# tivaAdapterPcb.net
KiCad netlist of a schematic drawn in EAGLE
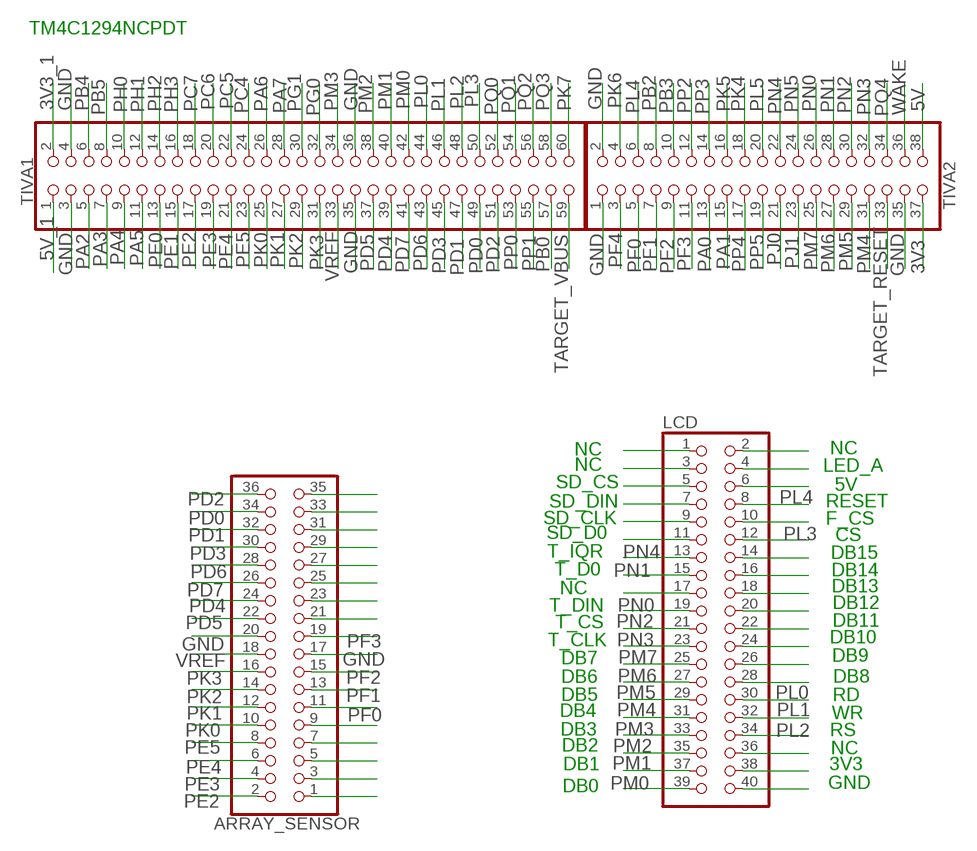
[diagram p0: schematic, sheet 1]

(export (version "E")
  (design (tool "Eeschema 10.0.6"))
  (components
    (comp (ref "ARRAY_SENSOR")
      (value "PINHD-2X18")
      (footprint "eagle-import:2X18")
      (libsource (lib "eagle-import") (part "PINHD-2X18"))
    )
    (comp (ref "LCD")
      (value "PINHD-2X20")
      (footprint "eagle-import:2X20")
      (libsource (lib "eagle-import") (part "PINHD-2X20"))
    )
    (comp (ref "TIVA1")
      (value "PINHD-2X30")
      (footprint "eagle-import:2X30")
      (libsource (lib "eagle-import") (part "PINHD-2X30"))
    )
    (comp (ref "TIVA2")
      (value "PINHD-2X19")
      (footprint "eagle-import:2X19")
      (libsource (lib "eagle-import") (part "PINHD-2X19"))
    )
  )
  (nets
    (net (code "1") (name "/3V3") (class "Default")
      (node (ref "TIVA2") (pin "37") (pinfunction "37_37") (pintype "passive"))
    )
    (net (code "2") (name "/3V3_1") (class "Default")
      (node (ref "TIVA1") (pin "2") (pinfunction "2_2") (pintype "passive"))
    )
    (net (code "3") (name "/5V") (class "Default")
      (node (ref "TIVA2") (pin "38") (pinfunction "38_38") (pintype "passive"))
    )
    (net (code "4") (name "/5V_1") (class "Default")
      (node (ref "TIVA1") (pin "1") (pinfunction "1_1") (pintype "passive"))
    )
    (net (code "5") (name "/GND") (class "Default")
      (node (ref "ARRAY_SENSOR") (pin "17") (pinfunction "17_17") (pintype "passive"))
      (node (ref "ARRAY_SENSOR") (pin "20") (pinfunction "20_20") (pintype "passive"))
      (node (ref "TIVA1") (pin "3") (pinfunction "3_3") (pintype "passive"))
      (node (ref "TIVA1") (pin "35") (pinfunction "35_35") (pintype "passive"))
      (node (ref "TIVA1") (pin "36") (pinfunction "36_36") (pintype "passive"))
      (node (ref "TIVA1") (pin "4") (pinfunction "4_4") (pintype "passive"))
      (node (ref "TIVA2") (pin "1") (pinfunction "1_1") (pintype "passive"))
      (node (ref "TIVA2") (pin "2") (pinfunction "2_2") (pintype "passive"))
      (node (ref "TIVA2") (pin "35") (pinfunction "35_35") (pintype "passive"))
    )
    (net (code "6") (name "/PA0") (class "Default")
      (node (ref "TIVA2") (pin "13") (pinfunction "13_13") (pintype "passive"))
    )
    (net (code "7") (name "/PA1") (class "Default")
      (node (ref "TIVA2") (pin "15") (pinfunction "15_15") (pintype "passive"))
    )
    (net (code "8") (name "/PA2") (class "Default")
      (node (ref "TIVA1") (pin "5") (pinfunction "5_5") (pintype "passive"))
    )
    (net (code "9") (name "/PA3") (class "Default")
      (node (ref "TIVA1") (pin "7") (pinfunction "7_7") (pintype "passive"))
    )
    (net (code "10") (name "/PA4") (class "Default")
      (node (ref "TIVA1") (pin "9") (pinfunction "9_9") (pintype "passive"))
    )
    (net (code "11") (name "/PA5") (class "Default")
      (node (ref "TIVA1") (pin "11") (pinfunction "11_11") (pintype "passive"))
    )
    (net (code "12") (name "/PA6") (class "Default")
      (node (ref "TIVA1") (pin "26") (pinfunction "26_26") (pintype "passive"))
    )
    (net (code "13") (name "/PA7") (class "Default")
      (node (ref "TIVA1") (pin "28") (pinfunction "28_28") (pintype "passive"))
    )
    (net (code "14") (name "/PB0") (class "Default")
      (node (ref "TIVA1") (pin "57") (pinfunction "57_57") (pintype "passive"))
    )
    (net (code "15") (name "/PB2") (class "Default")
      (node (ref "TIVA2") (pin "8") (pinfunction "8_8") (pintype "passive"))
    )
    (net (code "16") (name "/PB3") (class "Default")
      (node (ref "TIVA2") (pin "10") (pinfunction "10_10") (pintype "passive"))
    )
    (net (code "17") (name "/PB4") (class "Default")
      (node (ref "TIVA1") (pin "6") (pinfunction "6_6") (pintype "passive"))
    )
    (net (code "18") (name "/PB5") (class "Default")
      (node (ref "TIVA1") (pin "8") (pinfunction "8_8") (pintype "passive"))
    )
    (net (code "19") (name "/PC4") (class "Default")
      (node (ref "TIVA1") (pin "24") (pinfunction "24_24") (pintype "passive"))
    )
    (net (code "20") (name "/PC5") (class "Default")
      (node (ref "TIVA1") (pin "22") (pinfunction "22_22") (pintype "passive"))
    )
    (net (code "21") (name "/PC6") (class "Default")
      (node (ref "TIVA1") (pin "20") (pinfunction "20_20") (pintype "passive"))
    )
    (net (code "22") (name "/PC7") (class "Default")
      (node (ref "TIVA1") (pin "18") (pinfunction "18_18") (pintype "passive"))
    )
    (net (code "23") (name "/PD0") (class "Default")
      (node (ref "ARRAY_SENSOR") (pin "34") (pinfunction "34_34") (pintype "passive"))
      (node (ref "TIVA1") (pin "49") (pinfunction "49_49") (pintype "passive"))
    )
    (net (code "24") (name "/PD1") (class "Default")
      (node (ref "ARRAY_SENSOR") (pin "32") (pinfunction "32_32") (pintype "passive"))
      (node (ref "TIVA1") (pin "47") (pinfunction "47_47") (pintype "passive"))
    )
    (net (code "25") (name "/PD2") (class "Default")
      (node (ref "ARRAY_SENSOR") (pin "36") (pinfunction "36_36") (pintype "passive"))
      (node (ref "TIVA1") (pin "51") (pinfunction "51_51") (pintype "passive"))
    )
    (net (code "26") (name "/PD3") (class "Default")
      (node (ref "ARRAY_SENSOR") (pin "30") (pinfunction "30_30") (pintype "passive"))
      (node (ref "TIVA1") (pin "45") (pinfunction "45_45") (pintype "passive"))
    )
    (net (code "27") (name "/PD4") (class "Default")
      (node (ref "ARRAY_SENSOR") (pin "24") (pinfunction "24_24") (pintype "passive"))
      (node (ref "TIVA1") (pin "39") (pinfunction "39_39") (pintype "passive"))
    )
    (net (code "28") (name "/PD5") (class "Default")
      (node (ref "ARRAY_SENSOR") (pin "22") (pinfunction "22_22") (pintype "passive"))
      (node (ref "TIVA1") (pin "37") (pinfunction "37_37") (pintype "passive"))
    )
    (net (code "29") (name "/PD6") (class "Default")
      (node (ref "ARRAY_SENSOR") (pin "28") (pinfunction "28_28") (pintype "passive"))
      (node (ref "TIVA1") (pin "43") (pinfunction "43_43") (pintype "passive"))
    )
    (net (code "30") (name "/PD7") (class "Default")
      (node (ref "ARRAY_SENSOR") (pin "26") (pinfunction "26_26") (pintype "passive"))
      (node (ref "TIVA1") (pin "41") (pinfunction "41_41") (pintype "passive"))
    )
    (net (code "31") (name "/PE0") (class "Default")
      (node (ref "TIVA1") (pin "13") (pinfunction "13_13") (pintype "passive"))
    )
    (net (code "32") (name "/PE1") (class "Default")
      (node (ref "TIVA1") (pin "15") (pinfunction "15_15") (pintype "passive"))
    )
    (net (code "33") (name "/PE2") (class "Default")
      (node (ref "ARRAY_SENSOR") (pin "2") (pinfunction "2_2") (pintype "passive"))
      (node (ref "TIVA1") (pin "17") (pinfunction "17_17") (pintype "passive"))
    )
    (net (code "34") (name "/PE3") (class "Default")
      (node (ref "ARRAY_SENSOR") (pin "4") (pinfunction "4_4") (pintype "passive"))
      (node (ref "TIVA1") (pin "19") (pinfunction "19_19") (pintype "passive"))
    )
    (net (code "35") (name "/PE4") (class "Default")
      (node (ref "ARRAY_SENSOR") (pin "6") (pinfunction "6_6") (pintype "passive"))
      (node (ref "TIVA1") (pin "21") (pinfunction "21_21") (pintype "passive"))
    )
    (net (code "36") (name "/PE5") (class "Default")
      (node (ref "ARRAY_SENSOR") (pin "8") (pinfunction "8_8") (pintype "passive"))
      (node (ref "TIVA1") (pin "23") (pinfunction "23_23") (pintype "passive"))
    )
    (net (code "37") (name "/PF0") (class "Default")
      (node (ref "ARRAY_SENSOR") (pin "11") (pinfunction "11_11") (pintype "passive"))
      (node (ref "TIVA2") (pin "5") (pinfunction "5_5") (pintype "passive"))
    )
    (net (code "38") (name "/PF1") (class "Default")
      (node (ref "ARRAY_SENSOR") (pin "13") (pinfunction "13_13") (pintype "passive"))
      (node (ref "TIVA2") (pin "7") (pinfunction "7_7") (pintype "passive"))
    )
    (net (code "39") (name "/PF2") (class "Default")
      (node (ref "ARRAY_SENSOR") (pin "15") (pinfunction "15_15") (pintype "passive"))
      (node (ref "TIVA2") (pin "9") (pinfunction "9_9") (pintype "passive"))
    )
    (net (code "40") (name "/PF3") (class "Default")
      (node (ref "ARRAY_SENSOR") (pin "19") (pinfunction "19_19") (pintype "passive"))
      (node (ref "TIVA2") (pin "11") (pinfunction "11_11") (pintype "passive"))
    )
    (net (code "41") (name "/PF4") (class "Default")
      (node (ref "TIVA2") (pin "3") (pinfunction "3_3") (pintype "passive"))
    )
    (net (code "42") (name "/PG0") (class "Default")
      (node (ref "TIVA1") (pin "32") (pinfunction "32_32") (pintype "passive"))
    )
    (net (code "43") (name "/PG1") (class "Default")
      (node (ref "TIVA1") (pin "30") (pinfunction "30_30") (pintype "passive"))
    )
    (net (code "44") (name "/PH0") (class "Default")
      (node (ref "TIVA1") (pin "10") (pinfunction "10_10") (pintype "passive"))
    )
    (net (code "45") (name "/PH1") (class "Default")
      (node (ref "TIVA1") (pin "12") (pinfunction "12_12") (pintype "passive"))
    )
    (net (code "46") (name "/PH2") (class "Default")
      (node (ref "TIVA1") (pin "14") (pinfunction "14_14") (pintype "passive"))
    )
    (net (code "47") (name "/PH3") (class "Default")
      (node (ref "TIVA1") (pin "16") (pinfunction "16_16") (pintype "passive"))
    )
    (net (code "48") (name "/PJ0") (class "Default")
      (node (ref "TIVA2") (pin "21") (pinfunction "21_21") (pintype "passive"))
    )
    (net (code "49") (name "/PJ1") (class "Default")
      (node (ref "TIVA2") (pin "23") (pinfunction "23_23") (pintype "passive"))
    )
    (net (code "50") (name "/PK0") (class "Default")
      (node (ref "ARRAY_SENSOR") (pin "10") (pinfunction "10_10") (pintype "passive"))
      (node (ref "TIVA1") (pin "25") (pinfunction "25_25") (pintype "passive"))
    )
    (net (code "51") (name "/PK1") (class "Default")
      (node (ref "ARRAY_SENSOR") (pin "12") (pinfunction "12_12") (pintype "passive"))
      (node (ref "TIVA1") (pin "27") (pinfunction "27_27") (pintype "passive"))
    )
    (net (code "52") (name "/PK2") (class "Default")
      (node (ref "ARRAY_SENSOR") (pin "14") (pinfunction "14_14") (pintype "passive"))
      (node (ref "TIVA1") (pin "29") (pinfunction "29_29") (pintype "passive"))
    )
    (net (code "53") (name "/PK3") (class "Default")
      (node (ref "ARRAY_SENSOR") (pin "16") (pinfunction "16_16") (pintype "passive"))
      (node (ref "TIVA1") (pin "31") (pinfunction "31_31") (pintype "passive"))
    )
    (net (code "54") (name "/PK4") (class "Default")
      (node (ref "TIVA2") (pin "18") (pinfunction "18_18") (pintype "passive"))
    )
    (net (code "55") (name "/PK5") (class "Default")
      (node (ref "TIVA2") (pin "16") (pinfunction "16_16") (pintype "passive"))
    )
    (net (code "56") (name "/PK6") (class "Default")
      (node (ref "TIVA2") (pin "4") (pinfunction "4_4") (pintype "passive"))
    )
    (net (code "57") (name "/PK7") (class "Default")
      (node (ref "TIVA1") (pin "60") (pinfunction "60_60") (pintype "passive"))
    )
    (net (code "58") (name "/PL0") (class "Default")
      (node (ref "LCD") (pin "30") (pinfunction "30_30") (pintype "passive"))
      (node (ref "TIVA1") (pin "44") (pinfunction "44_44") (pintype "passive"))
    )
    (net (code "59") (name "/PL1") (class "Default")
      (node (ref "LCD") (pin "32") (pinfunction "32_32") (pintype "passive"))
      (node (ref "TIVA1") (pin "46") (pinfunction "46_46") (pintype "passive"))
    )
    (net (code "60") (name "/PL2") (class "Default")
      (node (ref "LCD") (pin "34") (pinfunction "34_34") (pintype "passive"))
      (node (ref "TIVA1") (pin "48") (pinfunction "48_48") (pintype "passive"))
    )
    (net (code "61") (name "/PL3") (class "Default")
      (node (ref "LCD") (pin "12") (pinfunction "12_12") (pintype "passive"))
      (node (ref "TIVA1") (pin "50") (pinfunction "50_50") (pintype "passive"))
    )
    (net (code "62") (name "/PL4") (class "Default")
      (node (ref "LCD") (pin "8") (pinfunction "8_8") (pintype "passive"))
      (node (ref "TIVA2") (pin "6") (pinfunction "6_6") (pintype "passive"))
    )
    (net (code "63") (name "/PL5") (class "Default")
      (node (ref "TIVA2") (pin "20") (pinfunction "20_20") (pintype "passive"))
    )
    (net (code "64") (name "/PM0") (class "Default")
      (node (ref "LCD") (pin "39") (pinfunction "39_39") (pintype "passive"))
      (node (ref "TIVA1") (pin "42") (pinfunction "42_42") (pintype "passive"))
    )
    (net (code "65") (name "/PM1") (class "Default")
      (node (ref "LCD") (pin "37") (pinfunction "37_37") (pintype "passive"))
      (node (ref "TIVA1") (pin "40") (pinfunction "40_40") (pintype "passive"))
    )
    (net (code "66") (name "/PM2") (class "Default")
      (node (ref "LCD") (pin "35") (pinfunction "35_35") (pintype "passive"))
      (node (ref "TIVA1") (pin "38") (pinfunction "38_38") (pintype "passive"))
    )
    (net (code "67") (name "/PM3") (class "Default")
      (node (ref "LCD") (pin "33") (pinfunction "33_33") (pintype "passive"))
      (node (ref "TIVA1") (pin "34") (pinfunction "34_34") (pintype "passive"))
    )
    (net (code "68") (name "/PM4") (class "Default")
      (node (ref "LCD") (pin "31") (pinfunction "31_31") (pintype "passive"))
      (node (ref "TIVA2") (pin "31") (pinfunction "31_31") (pintype "passive"))
    )
    (net (code "69") (name "/PM5") (class "Default")
      (node (ref "LCD") (pin "29") (pinfunction "29_29") (pintype "passive"))
      (node (ref "TIVA2") (pin "29") (pinfunction "29_29") (pintype "passive"))
    )
    (net (code "70") (name "/PM6") (class "Default")
      (node (ref "LCD") (pin "27") (pinfunction "27_27") (pintype "passive"))
      (node (ref "TIVA2") (pin "27") (pinfunction "27_27") (pintype "passive"))
    )
    (net (code "71") (name "/PM7") (class "Default")
      (node (ref "LCD") (pin "25") (pinfunction "25_25") (pintype "passive"))
      (node (ref "TIVA2") (pin "25") (pinfunction "25_25") (pintype "passive"))
    )
    (net (code "72") (name "/PN0") (class "Default")
      (node (ref "LCD") (pin "19") (pinfunction "19_19") (pintype "passive"))
      (node (ref "TIVA2") (pin "26") (pinfunction "26_26") (pintype "passive"))
    )
    (net (code "73") (name "/PN1") (class "Default")
      (node (ref "LCD") (pin "15") (pinfunction "15_15") (pintype "passive"))
      (node (ref "TIVA2") (pin "28") (pinfunction "28_28") (pintype "passive"))
    )
    (net (code "74") (name "/PN2") (class "Default")
      (node (ref "LCD") (pin "21") (pinfunction "21_21") (pintype "passive"))
      (node (ref "TIVA2") (pin "30") (pinfunction "30_30") (pintype "passive"))
    )
    (net (code "75") (name "/PN3") (class "Default")
      (node (ref "LCD") (pin "23") (pinfunction "23_23") (pintype "passive"))
      (node (ref "TIVA2") (pin "32") (pinfunction "32_32") (pintype "passive"))
    )
    (net (code "76") (name "/PN4") (class "Default")
      (node (ref "LCD") (pin "13") (pinfunction "13_13") (pintype "passive"))
      (node (ref "TIVA2") (pin "22") (pinfunction "22_22") (pintype "passive"))
    )
    (net (code "77") (name "/PN5") (class "Default")
      (node (ref "TIVA2") (pin "24") (pinfunction "24_24") (pintype "passive"))
    )
    (net (code "78") (name "/PP0") (class "Default")
      (node (ref "TIVA1") (pin "53") (pinfunction "53_53") (pintype "passive"))
    )
    (net (code "79") (name "/PP1") (class "Default")
      (node (ref "TIVA1") (pin "55") (pinfunction "55_55") (pintype "passive"))
    )
    (net (code "80") (name "/PP2") (class "Default")
      (node (ref "TIVA2") (pin "12") (pinfunction "12_12") (pintype "passive"))
    )
    (net (code "81") (name "/PP3") (class "Default")
      (node (ref "TIVA2") (pin "14") (pinfunction "14_14") (pintype "passive"))
    )
    (net (code "82") (name "/PP4") (class "Default")
      (node (ref "TIVA2") (pin "17") (pinfunction "17_17") (pintype "passive"))
    )
    (net (code "83") (name "/PP5") (class "Default")
      (node (ref "TIVA2") (pin "19") (pinfunction "19_19") (pintype "passive"))
    )
    (net (code "84") (name "/PQ0") (class "Default")
      (node (ref "TIVA1") (pin "52") (pinfunction "52_52") (pintype "passive"))
    )
    (net (code "85") (name "/PQ1") (class "Default")
      (node (ref "TIVA1") (pin "54") (pinfunction "54_54") (pintype "passive"))
    )
    (net (code "86") (name "/PQ2") (class "Default")
      (node (ref "TIVA1") (pin "56") (pinfunction "56_56") (pintype "passive"))
    )
    (net (code "87") (name "/PQ3") (class "Default")
      (node (ref "TIVA1") (pin "58") (pinfunction "58_58") (pintype "passive"))
    )
    (net (code "88") (name "/PQ4") (class "Default")
      (node (ref "TIVA2") (pin "34") (pinfunction "34_34") (pintype "passive"))
    )
    (net (code "89") (name "/TARGET_RESET") (class "Default")
      (node (ref "TIVA2") (pin "33") (pinfunction "33_33") (pintype "passive"))
    )
    (net (code "90") (name "/TARGET_VBUS") (class "Default")
      (node (ref "TIVA1") (pin "59") (pinfunction "59_59") (pintype "passive"))
    )
    (net (code "91") (name "/VREF") (class "Default")
      (node (ref "ARRAY_SENSOR") (pin "18") (pinfunction "18_18") (pintype "passive"))
      (node (ref "TIVA1") (pin "33") (pinfunction "33_33") (pintype "passive"))
    )
    (net (code "92") (name "/WAKE") (class "Default")
      (node (ref "TIVA2") (pin "36") (pinfunction "36_36") (pintype "passive"))
    )
    (net (code "93") (name "unconnected-(ARRAY_SENSOR-Pad1)") (class "Default")
      (node (ref "ARRAY_SENSOR") (pin "1") (pinfunction "1_1") (pintype "passive"))
    )
    (net (code "94") (name "unconnected-(ARRAY_SENSOR-Pad3)") (class "Default")
      (node (ref "ARRAY_SENSOR") (pin "3") (pinfunction "3_3") (pintype "passive"))
    )
    (net (code "95") (name "unconnected-(ARRAY_SENSOR-Pad5)") (class "Default")
      (node (ref "ARRAY_SENSOR") (pin "5") (pinfunction "5_5") (pintype "passive"))
    )
    (net (code "96") (name "unconnected-(ARRAY_SENSOR-Pad7)") (class "Default")
      (node (ref "ARRAY_SENSOR") (pin "7") (pinfunction "7_7") (pintype "passive"))
    )
    (net (code "97") (name "unconnected-(ARRAY_SENSOR-Pad9)") (class "Default")
      (node (ref "ARRAY_SENSOR") (pin "9") (pinfunction "9_9") (pintype "passive"))
    )
    (net (code "98") (name "unconnected-(ARRAY_SENSOR-Pad21)") (class "Default")
      (node (ref "ARRAY_SENSOR") (pin "21") (pinfunction "21_21") (pintype "passive"))
    )
    (net (code "99") (name "unconnected-(ARRAY_SENSOR-Pad23)") (class "Default")
      (node (ref "ARRAY_SENSOR") (pin "23") (pinfunction "23_23") (pintype "passive"))
    )
    (net (code "100") (name "unconnected-(ARRAY_SENSOR-Pad25)") (class "Default")
      (node (ref "ARRAY_SENSOR") (pin "25") (pinfunction "25_25") (pintype "passive"))
    )
    (net (code "101") (name "unconnected-(ARRAY_SENSOR-Pad27)") (class "Default")
      (node (ref "ARRAY_SENSOR") (pin "27") (pinfunction "27_27") (pintype "passive"))
    )
    (net (code "102") (name "unconnected-(ARRAY_SENSOR-Pad29)") (class "Default")
      (node (ref "ARRAY_SENSOR") (pin "29") (pinfunction "29_29") (pintype "passive"))
    )
    (net (code "103") (name "unconnected-(ARRAY_SENSOR-Pad31)") (class "Default")
      (node (ref "ARRAY_SENSOR") (pin "31") (pinfunction "31_31") (pintype "passive"))
    )
    (net (code "104") (name "unconnected-(ARRAY_SENSOR-Pad33)") (class "Default")
      (node (ref "ARRAY_SENSOR") (pin "33") (pinfunction "33_33") (pintype "passive"))
    )
    (net (code "105") (name "unconnected-(ARRAY_SENSOR-Pad35)") (class "Default")
      (node (ref "ARRAY_SENSOR") (pin "35") (pinfunction "35_35") (pintype "passive"))
    )
    (net (code "106") (name "unconnected-(LCD-Pad1)") (class "Default")
      (node (ref "LCD") (pin "1") (pinfunction "1_1") (pintype "passive"))
    )
    (net (code "107") (name "unconnected-(LCD-Pad2)") (class "Default")
      (node (ref "LCD") (pin "2") (pinfunction "2_2") (pintype "passive"))
    )
    (net (code "108") (name "unconnected-(LCD-Pad3)") (class "Default")
      (node (ref "LCD") (pin "3") (pinfunction "3_3") (pintype "passive"))
    )
    (net (code "109") (name "unconnected-(LCD-Pad4)") (class "Default")
      (node (ref "LCD") (pin "4") (pinfunction "4_4") (pintype "passive"))
    )
    (net (code "110") (name "unconnected-(LCD-Pad5)") (class "Default")
      (node (ref "LCD") (pin "5") (pinfunction "5_5") (pintype "passive"))
    )
    (net (code "111") (name "unconnected-(LCD-Pad6)") (class "Default")
      (node (ref "LCD") (pin "6") (pinfunction "6_6") (pintype "passive"))
    )
    (net (code "112") (name "unconnected-(LCD-Pad7)") (class "Default")
      (node (ref "LCD") (pin "7") (pinfunction "7_7") (pintype "passive"))
    )
    (net (code "113") (name "unconnected-(LCD-Pad9)") (class "Default")
      (node (ref "LCD") (pin "9") (pinfunction "9_9") (pintype "passive"))
    )
    (net (code "114") (name "unconnected-(LCD-Pad10)") (class "Default")
      (node (ref "LCD") (pin "10") (pinfunction "10_10") (pintype "passive"))
    )
    (net (code "115") (name "unconnected-(LCD-Pad11)") (class "Default")
      (node (ref "LCD") (pin "11") (pinfunction "11_11") (pintype "passive"))
    )
    (net (code "116") (name "unconnected-(LCD-Pad14)") (class "Default")
      (node (ref "LCD") (pin "14") (pinfunction "14_14") (pintype "passive"))
    )
    (net (code "117") (name "unconnected-(LCD-Pad16)") (class "Default")
      (node (ref "LCD") (pin "16") (pinfunction "16_16") (pintype "passive"))
    )
    (net (code "118") (name "unconnected-(LCD-Pad17)") (class "Default")
      (node (ref "LCD") (pin "17") (pinfunction "17_17") (pintype "passive"))
    )
    (net (code "119") (name "unconnected-(LCD-Pad18)") (class "Default")
      (node (ref "LCD") (pin "18") (pinfunction "18_18") (pintype "passive"))
    )
    (net (code "120") (name "unconnected-(LCD-Pad20)") (class "Default")
      (node (ref "LCD") (pin "20") (pinfunction "20_20") (pintype "passive"))
    )
    (net (code "121") (name "unconnected-(LCD-Pad22)") (class "Default")
      (node (ref "LCD") (pin "22") (pinfunction "22_22") (pintype "passive"))
    )
    (net (code "122") (name "unconnected-(LCD-Pad24)") (class "Default")
      (node (ref "LCD") (pin "24") (pinfunction "24_24") (pintype "passive"))
    )
    (net (code "123") (name "unconnected-(LCD-Pad26)") (class "Default")
      (node (ref "LCD") (pin "26") (pinfunction "26_26") (pintype "passive"))
    )
    (net (code "124") (name "unconnected-(LCD-Pad28)") (class "Default")
      (node (ref "LCD") (pin "28") (pinfunction "28_28") (pintype "passive"))
    )
    (net (code "125") (name "unconnected-(LCD-Pad36)") (class "Default")
      (node (ref "LCD") (pin "36") (pinfunction "36_36") (pintype "passive"))
    )
    (net (code "126") (name "unconnected-(LCD-Pad38)") (class "Default")
      (node (ref "LCD") (pin "38") (pinfunction "38_38") (pintype "passive"))
    )
    (net (code "127") (name "unconnected-(LCD-Pad40)") (class "Default")
      (node (ref "LCD") (pin "40") (pinfunction "40_40") (pintype "passive"))
    )
  )
)
